# ArqSAME70Comp.net
KiCad netlist of a schematic drawn in EAGLE
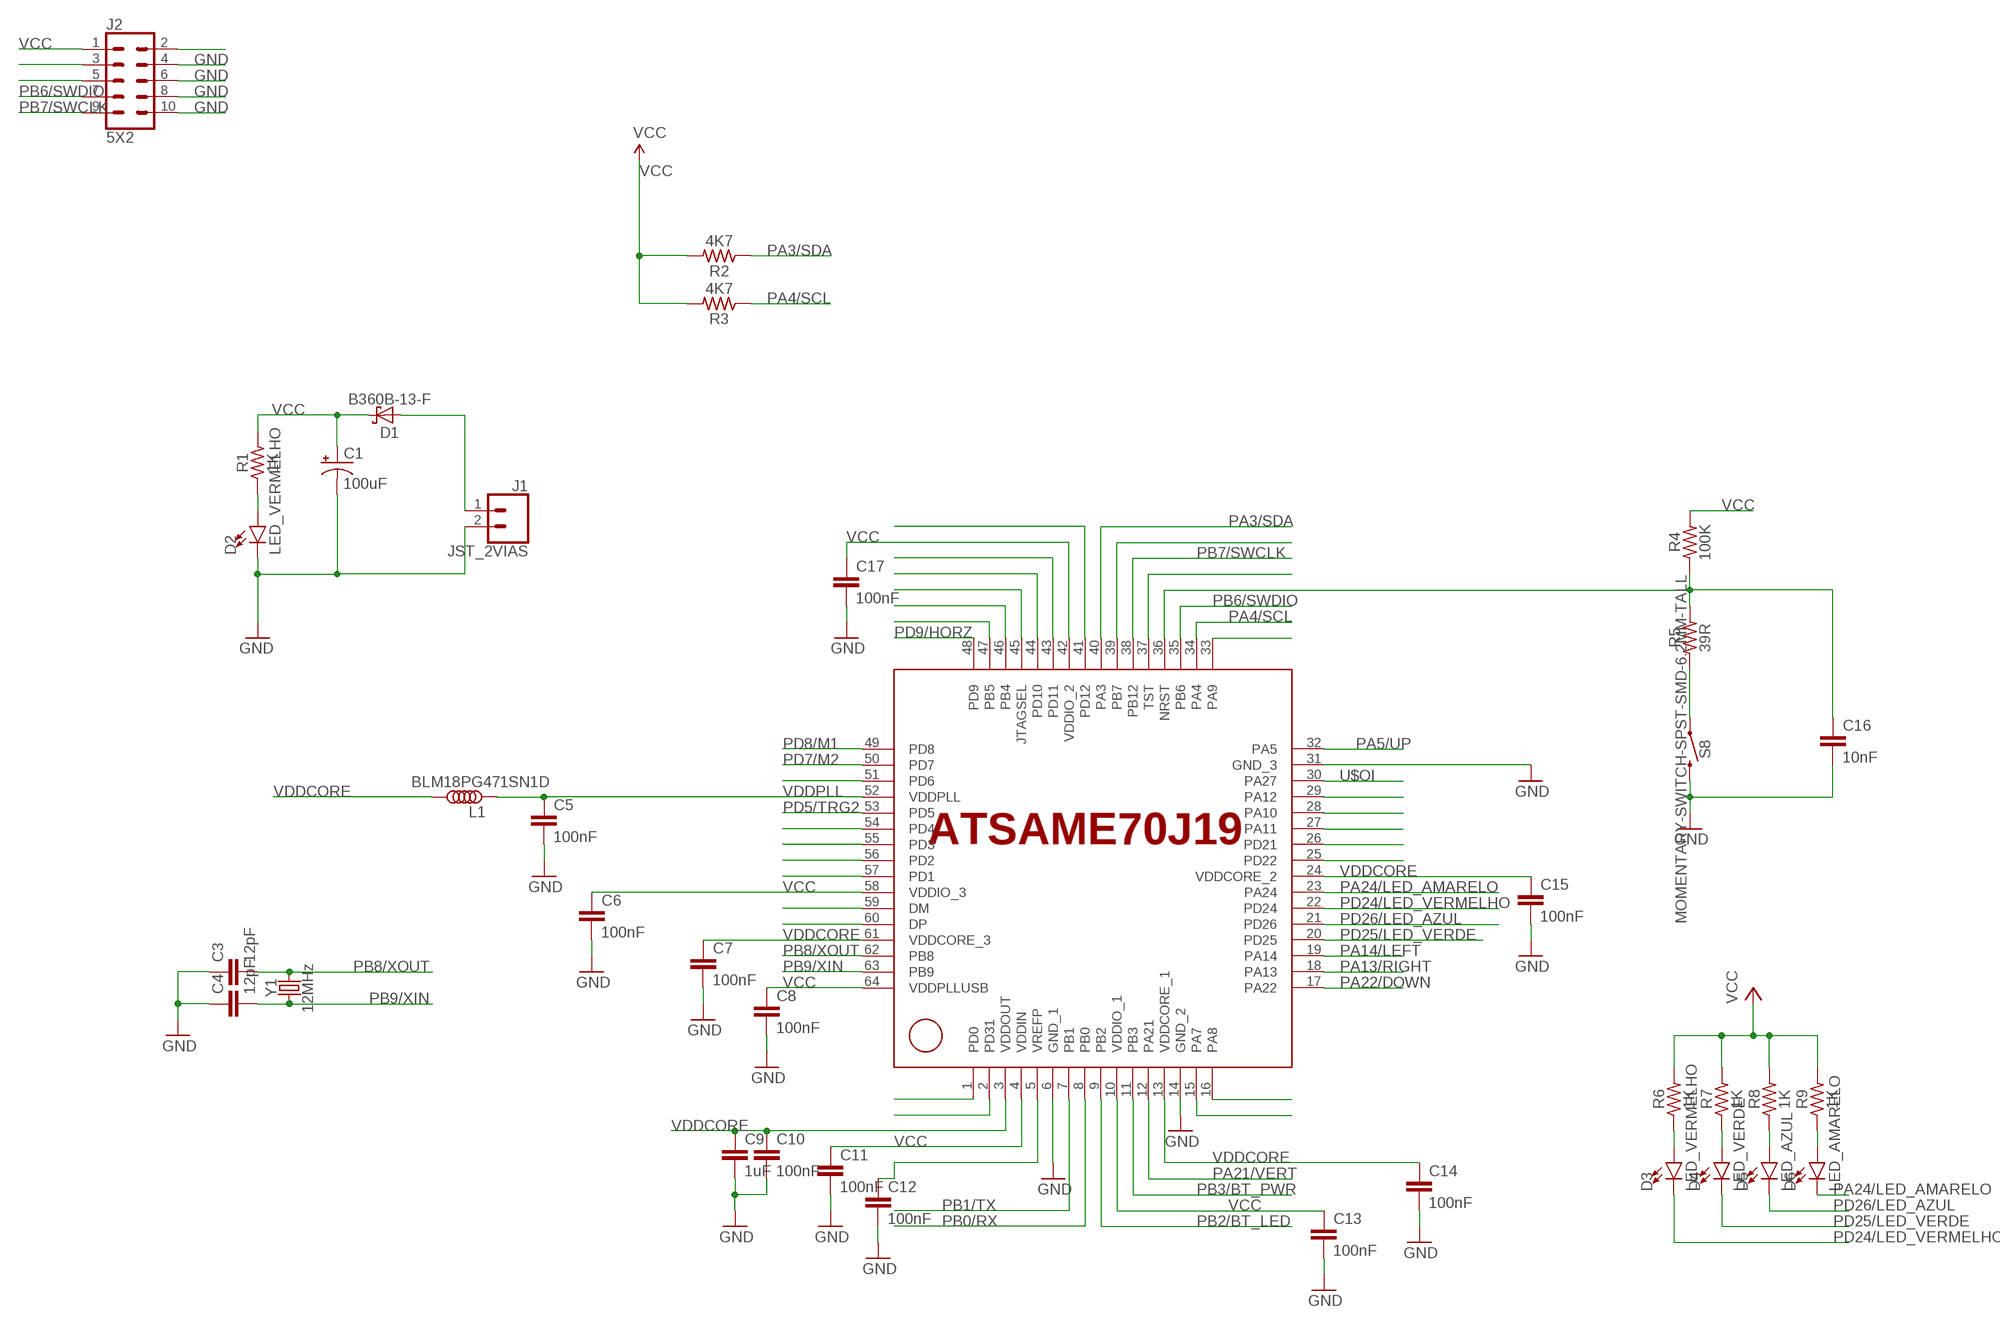
[diagram p0: schematic, sheet 1]

(export (version "E")
  (design (tool "Eeschema 10.0.6"))
  (components
    (comp (ref "C1")
      (value "100uF")
      (footprint "eagle-import:PANASONIC_D")
      (libsource (lib "eagle-import") (part "CAP_POLD"))
    )
    (comp (ref "C3")
      (value "12pF")
      (footprint "eagle-import:0603")
      (libsource (lib "eagle-import") (part "12PF-0603-50V-5%"))
    )
    (comp (ref "C4")
      (value "12pF")
      (footprint "eagle-import:0603")
      (libsource (lib "eagle-import") (part "12PF-0603-50V-5%"))
    )
    (comp (ref "C5")
      (value "100nF")
      (footprint "eagle-import:C0603K")
      (libsource (lib "eagle-import") (part "C-EUC0603K"))
    )
    (comp (ref "C6")
      (value "100nF")
      (footprint "eagle-import:C0603K")
      (libsource (lib "eagle-import") (part "C-EUC0603K"))
    )
    (comp (ref "C7")
      (value "100nF")
      (footprint "eagle-import:C0603K")
      (libsource (lib "eagle-import") (part "C-EUC0603K"))
    )
    (comp (ref "C8")
      (value "100nF")
      (footprint "eagle-import:C0603K")
      (libsource (lib "eagle-import") (part "C-EUC0603K"))
    )
    (comp (ref "C9")
      (value "1uF")
      (footprint "eagle-import:C0603K")
      (libsource (lib "eagle-import") (part "C-EUC0603K"))
    )
    (comp (ref "C10")
      (value "100nF")
      (footprint "eagle-import:C0603K")
      (libsource (lib "eagle-import") (part "C-EUC0603K"))
    )
    (comp (ref "C11")
      (value "100nF")
      (footprint "eagle-import:C0603K")
      (libsource (lib "eagle-import") (part "C-EUC0603K"))
    )
    (comp (ref "C12")
      (value "100nF")
      (footprint "eagle-import:C0603K")
      (libsource (lib "eagle-import") (part "C-EUC0603K"))
    )
    (comp (ref "C13")
      (value "100nF")
      (footprint "eagle-import:C0603K")
      (libsource (lib "eagle-import") (part "C-EUC0603K"))
    )
    (comp (ref "C14")
      (value "100nF")
      (footprint "eagle-import:C0603K")
      (libsource (lib "eagle-import") (part "C-EUC0603K"))
    )
    (comp (ref "C15")
      (value "100nF")
      (footprint "eagle-import:C0603K")
      (libsource (lib "eagle-import") (part "C-EUC0603K"))
    )
    (comp (ref "C16")
      (value "10nF")
      (footprint "eagle-import:C0603K")
      (libsource (lib "eagle-import") (part "C-EUC0603K"))
    )
    (comp (ref "C17")
      (value "100nF")
      (footprint "eagle-import:C0603K")
      (libsource (lib "eagle-import") (part "C-EUC0603K"))
    )
    (comp (ref "D1")
      (value "B360B-13-F")
      (footprint "eagle-import:DIODE_SMB")
      (libsource (lib "eagle-import") (part "SCHOTTKY-DIODE"))
    )
    (comp (ref "D2")
      (value "LED_VERMELHO")
      (footprint "eagle-import:LED-1206")
      (libsource (lib "eagle-import") (part "LED1206"))
    )
    (comp (ref "D3")
      (value "LED_VERMELHO")
      (footprint "eagle-import:LED-1206")
      (libsource (lib "eagle-import") (part "LED1206"))
    )
    (comp (ref "D4")
      (value "LED_VERDE")
      (footprint "eagle-import:LED-1206")
      (libsource (lib "eagle-import") (part "LED1206"))
    )
    (comp (ref "D5")
      (value "LED_AZUL")
      (footprint "eagle-import:LED-1206")
      (libsource (lib "eagle-import") (part "LED1206"))
    )
    (comp (ref "D6")
      (value "LED_AMARELO")
      (footprint "eagle-import:LED-1206")
      (libsource (lib "eagle-import") (part "LED1206"))
    )
    (comp (ref "J1")
      (value "JST_2VIAS")
      (footprint "eagle-import:JST-2-SMD")
      (libsource (lib "eagle-import") (part "CONN_02-JST-2MM-SMT"))
    )
    (comp (ref "J2")
      (value "5X2")
      (footprint "eagle-import:2X5")
      (libsource (lib "eagle-import") (part "CONN_5X2"))
    )
    (comp (ref "L1")
      (value "BLM18PG471SN1D")
      (footprint "eagle-import:PACKAGE_0603")
      (libsource (lib "eagle-import") (part "FERRITE_0603"))
    )
    (comp (ref "R1")
      (value "1K")
      (footprint "eagle-import:R0603")
      (libsource (lib "eagle-import") (part "R-US_R0603"))
    )
    (comp (ref "R2")
      (value "4K7")
      (footprint "eagle-import:R0603")
      (libsource (lib "eagle-import") (part "R-US_R0603"))
    )
    (comp (ref "R3")
      (value "4K7")
      (footprint "eagle-import:R0603")
      (libsource (lib "eagle-import") (part "R-US_R0603"))
    )
    (comp (ref "R4")
      (value "100K")
      (footprint "eagle-import:R0603")
      (libsource (lib "eagle-import") (part "R-US_R0603"))
    )
    (comp (ref "R5")
      (value "39R")
      (footprint "eagle-import:R0603")
      (libsource (lib "eagle-import") (part "R-US_R0603"))
    )
    (comp (ref "R6")
      (value "1K")
      (footprint "eagle-import:R0603")
      (libsource (lib "eagle-import") (part "R-US_R0603"))
    )
    (comp (ref "R7")
      (value "1K")
      (footprint "eagle-import:R0603")
      (libsource (lib "eagle-import") (part "R-US_R0603"))
    )
    (comp (ref "R8")
      (value "1K")
      (footprint "eagle-import:R0603")
      (libsource (lib "eagle-import") (part "R-US_R0603"))
    )
    (comp (ref "R9")
      (value "1K")
      (footprint "eagle-import:R0603")
      (libsource (lib "eagle-import") (part "R-US_R0603"))
    )
    (comp (ref "S8")
      (value "MOMENTARY-SWITCH-SPST-SMD-6.2MM-TALL")
      (footprint "eagle-import:TACTILE_SWITCH_SMD_6.2MM_TALL")
      (libsource (lib "eagle-import") (part "MOMENTARY-SWITCH-SPST-SMD-6.2MM-TALL"))
    )
    (comp (ref "UC")
      (value "ATSAME70J19_LQFP64")
      (footprint "eagle-import:LQFP64")
      (libsource (lib "eagle-import") (part "ATSAME70J19LQFP64"))
    )
    (comp (ref "Y1")
      (value "12MHz")
      (footprint "eagle-import:CRYSTAL-SMD-5X3.2-4PAD")
      (libsource (lib "eagle-import") (part "CRYSTAL-12MHZ{dblquote}"))
    )
  )
  (nets
    (net (code "1") (name "/PA3{slash}SDA") (class "Default")
      (node (ref "R2") (pin "1") (pinfunction "1_1") (pintype "passive"))
      (node (ref "UC") (pin "40") (pinfunction "PA3_40") (pintype "output"))
    )
    (net (code "2") (name "/PA4{slash}SCL") (class "Default")
      (node (ref "R3") (pin "1") (pinfunction "1_1") (pintype "passive"))
      (node (ref "UC") (pin "34") (pinfunction "PA4_34") (pintype "input"))
    )
    (net (code "3") (name "/PA5{slash}UP") (class "Default")
      (node (ref "UC") (pin "32") (pinfunction "PA5_32") (pintype "input"))
    )
    (net (code "4") (name "/PA13{slash}RIGHT") (class "Default")
      (node (ref "UC") (pin "18") (pinfunction "PA13_18") (pintype "power_in"))
    )
    (net (code "5") (name "/PA14{slash}LEFT") (class "Default")
      (node (ref "UC") (pin "19") (pinfunction "PA14_19") (pintype "output"))
    )
    (net (code "6") (name "/PA21{slash}VERT") (class "Default")
      (node (ref "UC") (pin "12") (pinfunction "PA21_12") (pintype "input"))
    )
    (net (code "7") (name "/PA22{slash}DOWN") (class "Default")
      (node (ref "UC") (pin "17") (pinfunction "PA22_17") (pintype "power_in"))
    )
    (net (code "8") (name "/PA24{slash}LED_AMARELO") (class "Default")
      (node (ref "D6") (pin "C") (pinfunction "C_C") (pintype "passive"))
      (node (ref "UC") (pin "23") (pinfunction "PA24_23") (pintype "output"))
    )
    (net (code "9") (name "/PB0{slash}RX") (class "Default")
      (node (ref "UC") (pin "8") (pinfunction "PB0_8") (pintype "output"))
    )
    (net (code "10") (name "/PB1{slash}TX") (class "Default")
      (node (ref "UC") (pin "7") (pinfunction "PB1_7") (pintype "output"))
    )
    (net (code "11") (name "/PB2{slash}BT_LED") (class "Default")
      (node (ref "UC") (pin "9") (pinfunction "PB2_9") (pintype "power_in"))
    )
    (net (code "12") (name "/PB3{slash}BT_PWR") (class "Default")
      (node (ref "UC") (pin "11") (pinfunction "PB3_11") (pintype "power_in"))
    )
    (net (code "13") (name "/PB6{slash}SWDIO") (class "Default")
      (node (ref "J2") (pin "7") (pinfunction "7_7") (pintype "passive"))
      (node (ref "UC") (pin "35") (pinfunction "PB6_35") (pintype "input"))
    )
    (net (code "14") (name "/PB7{slash}SWCLK") (class "Default")
      (node (ref "J2") (pin "9") (pinfunction "9_9") (pintype "passive"))
      (node (ref "UC") (pin "39") (pinfunction "PB7_39") (pintype "input"))
    )
    (net (code "15") (name "/PB8{slash}XOUT") (class "Default")
      (node (ref "C3") (pin "2") (pinfunction "2_2") (pintype "passive"))
      (node (ref "UC") (pin "62") (pinfunction "PB8_62") (pintype "output"))
      (node (ref "Y1") (pin "3") (pinfunction "2_3") (pintype "passive"))
    )
    (net (code "16") (name "/PB9{slash}XIN") (class "Default")
      (node (ref "C4") (pin "2") (pinfunction "2_2") (pintype "passive"))
      (node (ref "UC") (pin "63") (pinfunction "PB9_63") (pintype "output"))
      (node (ref "Y1") (pin "1") (pinfunction "1_1") (pintype "passive"))
    )
    (net (code "17") (name "/PD5{slash}TRG2") (class "Default")
      (node (ref "UC") (pin "53") (pinfunction "PD5_53") (pintype "input"))
    )
    (net (code "18") (name "/PD7{slash}M2") (class "Default")
      (node (ref "UC") (pin "50") (pinfunction "PD7_50") (pintype "input"))
    )
    (net (code "19") (name "/PD8{slash}M1") (class "Default")
      (node (ref "UC") (pin "49") (pinfunction "PD8_49") (pintype "input"))
    )
    (net (code "20") (name "/PD9{slash}HORZ") (class "Default")
      (node (ref "UC") (pin "48") (pinfunction "PD9_48") (pintype "input"))
    )
    (net (code "21") (name "/PD24{slash}LED_VERMELHO") (class "Default")
      (node (ref "D3") (pin "C") (pinfunction "C_C") (pintype "passive"))
      (node (ref "UC") (pin "22") (pinfunction "PD24_22") (pintype "power_in"))
    )
    (net (code "22") (name "/PD25{slash}LED_VERDE") (class "Default")
      (node (ref "D4") (pin "C") (pinfunction "C_C") (pintype "passive"))
      (node (ref "UC") (pin "20") (pinfunction "PD25_20") (pintype "input"))
    )
    (net (code "23") (name "/PD26{slash}LED_AZUL") (class "Default")
      (node (ref "D5") (pin "C") (pinfunction "C_C") (pintype "passive"))
      (node (ref "UC") (pin "21") (pinfunction "PD26_21") (pintype "power_in"))
    )
    (net (code "24") (name "/U$OI") (class "Default")
      (node (ref "UC") (pin "30") (pinfunction "PA27_30") (pintype "input"))
    )
    (net (code "25") (name "/VDDCORE") (class "Default")
      (node (ref "C10") (pin "1") (pinfunction "1_1") (pintype "passive"))
      (node (ref "C14") (pin "1") (pinfunction "1_1") (pintype "passive"))
      (node (ref "C15") (pin "1") (pinfunction "1_1") (pintype "passive"))
      (node (ref "C7") (pin "1") (pinfunction "1_1") (pintype "passive"))
      (node (ref "C9") (pin "1") (pinfunction "1_1") (pintype "passive"))
      (node (ref "L1") (pin "2") (pinfunction "2_2") (pintype "passive"))
      (node (ref "UC") (pin "13") (pinfunction "VDDCORE_1_13") (pintype "input"))
      (node (ref "UC") (pin "24") (pinfunction "VDDCORE_2_24") (pintype "output"))
      (node (ref "UC") (pin "3") (pinfunction "VDDOUT_3") (pintype "output"))
      (node (ref "UC") (pin "61") (pinfunction "VDDCORE_3_61") (pintype "output"))
    )
    (net (code "26") (name "/VDDPLL") (class "Default")
      (node (ref "C5") (pin "1") (pinfunction "1_1") (pintype "passive"))
      (node (ref "L1") (pin "1") (pinfunction "1_1") (pintype "passive"))
      (node (ref "UC") (pin "52") (pinfunction "VDDPLL_52") (pintype "input"))
    )
    (net (code "27") (name "GND") (class "Default")
      (node (ref "C1") (pin "-") (pinfunction "-_-") (pintype "passive"))
      (node (ref "C10") (pin "2") (pinfunction "2_2") (pintype "passive"))
      (node (ref "C11") (pin "2") (pinfunction "2_2") (pintype "passive"))
      (node (ref "C12") (pin "2") (pinfunction "2_2") (pintype "passive"))
      (node (ref "C13") (pin "2") (pinfunction "2_2") (pintype "passive"))
      (node (ref "C14") (pin "2") (pinfunction "2_2") (pintype "passive"))
      (node (ref "C15") (pin "2") (pinfunction "2_2") (pintype "passive"))
      (node (ref "C16") (pin "2") (pinfunction "2_2") (pintype "passive"))
      (node (ref "C17") (pin "2") (pinfunction "2_2") (pintype "passive"))
      (node (ref "C3") (pin "1") (pinfunction "1_1") (pintype "passive"))
      (node (ref "C4") (pin "1") (pinfunction "1_1") (pintype "passive"))
      (node (ref "C5") (pin "2") (pinfunction "2_2") (pintype "passive"))
      (node (ref "C6") (pin "2") (pinfunction "2_2") (pintype "passive"))
      (node (ref "C7") (pin "2") (pinfunction "2_2") (pintype "passive"))
      (node (ref "C8") (pin "2") (pinfunction "2_2") (pintype "passive"))
      (node (ref "C9") (pin "2") (pinfunction "2_2") (pintype "passive"))
      (node (ref "D2") (pin "C") (pinfunction "C_C") (pintype "passive"))
      (node (ref "J1") (pin "2") (pinfunction "1_2") (pintype "passive"))
      (node (ref "J2") (pin "10") (pinfunction "10_10") (pintype "passive"))
      (node (ref "J2") (pin "4") (pinfunction "4_4") (pintype "passive"))
      (node (ref "J2") (pin "6") (pinfunction "6_6") (pintype "passive"))
      (node (ref "J2") (pin "8") (pinfunction "8_8") (pintype "passive"))
      (node (ref "S8") (pin "B2") (pinfunction "2_B2") (pintype "passive"))
      (node (ref "UC") (pin "14") (pinfunction "GND_2_14") (pintype "input"))
      (node (ref "UC") (pin "31") (pinfunction "GND_3_31") (pintype "input"))
      (node (ref "UC") (pin "6") (pinfunction "GND_1_6") (pintype "output"))
    )
    (net (code "28") (name "Net-(D1-C)") (class "Default")
      (node (ref "D1") (pin "A") (pinfunction "C_A") (pintype "passive"))
      (node (ref "J1") (pin "1") (pinfunction "2_1") (pintype "passive"))
    )
    (net (code "29") (name "Net-(D2-PadA)") (class "Default")
      (node (ref "D2") (pin "A") (pinfunction "A_A") (pintype "passive"))
      (node (ref "R1") (pin "1") (pinfunction "1_1") (pintype "passive"))
    )
    (net (code "30") (name "Net-(D3-PadA)") (class "Default")
      (node (ref "D3") (pin "A") (pinfunction "A_A") (pintype "passive"))
      (node (ref "R6") (pin "1") (pinfunction "1_1") (pintype "passive"))
    )
    (net (code "31") (name "Net-(D4-PadA)") (class "Default")
      (node (ref "D4") (pin "A") (pinfunction "A_A") (pintype "passive"))
      (node (ref "R7") (pin "1") (pinfunction "1_1") (pintype "passive"))
    )
    (net (code "32") (name "Net-(D5-PadA)") (class "Default")
      (node (ref "D5") (pin "A") (pinfunction "A_A") (pintype "passive"))
      (node (ref "R8") (pin "1") (pinfunction "1_1") (pintype "passive"))
    )
    (net (code "33") (name "Net-(D6-PadA)") (class "Default")
      (node (ref "D6") (pin "A") (pinfunction "A_A") (pintype "passive"))
      (node (ref "R9") (pin "1") (pinfunction "1_1") (pintype "passive"))
    )
    (net (code "34") (name "Net-(S8-1)") (class "Default")
      (node (ref "R5") (pin "1") (pinfunction "1_1") (pintype "passive"))
      (node (ref "S8") (pin "A2") (pinfunction "1_A2") (pintype "passive"))
    )
    (net (code "35") (name "Net-(UC-NRST)") (class "Default")
      (node (ref "C16") (pin "1") (pinfunction "1_1") (pintype "passive"))
      (node (ref "R4") (pin "1") (pinfunction "1_1") (pintype "passive"))
      (node (ref "R5") (pin "2") (pinfunction "2_2") (pintype "passive"))
      (node (ref "UC") (pin "36") (pinfunction "NRST_36") (pintype "power_in"))
    )
    (net (code "36") (name "Net-(UC-VREFP)") (class "Default")
      (node (ref "C12") (pin "1") (pinfunction "1_1") (pintype "passive"))
      (node (ref "UC") (pin "5") (pinfunction "VREFP_5") (pintype "output"))
    )
    (net (code "37") (name "VCC") (class "Default")
      (node (ref "C1") (pin "+") (pinfunction "+_+") (pintype "passive"))
      (node (ref "C11") (pin "1") (pinfunction "1_1") (pintype "passive"))
      (node (ref "C13") (pin "1") (pinfunction "1_1") (pintype "passive"))
      (node (ref "C17") (pin "1") (pinfunction "1_1") (pintype "passive"))
      (node (ref "C6") (pin "1") (pinfunction "1_1") (pintype "passive"))
      (node (ref "C8") (pin "1") (pinfunction "1_1") (pintype "passive"))
      (node (ref "D1") (pin "C") (pinfunction "A_C") (pintype "passive"))
      (node (ref "J2") (pin "1") (pinfunction "1_1") (pintype "passive"))
      (node (ref "R1") (pin "2") (pinfunction "2_2") (pintype "passive"))
      (node (ref "R2") (pin "2") (pinfunction "2_2") (pintype "passive"))
      (node (ref "R3") (pin "2") (pinfunction "2_2") (pintype "passive"))
      (node (ref "R4") (pin "2") (pinfunction "2_2") (pintype "passive"))
      (node (ref "R6") (pin "2") (pinfunction "2_2") (pintype "passive"))
      (node (ref "R7") (pin "2") (pinfunction "2_2") (pintype "passive"))
      (node (ref "R8") (pin "2") (pinfunction "2_2") (pintype "passive"))
      (node (ref "R9") (pin "2") (pinfunction "2_2") (pintype "passive"))
      (node (ref "UC") (pin "10") (pinfunction "VDDIO_1_10") (pintype "input"))
      (node (ref "UC") (pin "4") (pinfunction "VDDIN_4") (pintype "output"))
      (node (ref "UC") (pin "42") (pinfunction "VDDIO_2_42") (pintype "output"))
      (node (ref "UC") (pin "58") (pinfunction "VDDIO_3_58") (pintype "input"))
      (node (ref "UC") (pin "64") (pinfunction "VDDPLLUSB_64") (pintype "input"))
    )
    (net (code "38") (name "unconnected-(J2-Pad2)") (class "Default")
      (node (ref "J2") (pin "2") (pinfunction "2_2") (pintype "passive"))
    )
    (net (code "39") (name "unconnected-(J2-Pad3)") (class "Default")
      (node (ref "J2") (pin "3") (pinfunction "3_3") (pintype "passive"))
    )
    (net (code "40") (name "unconnected-(J2-Pad5)") (class "Default")
      (node (ref "J2") (pin "5") (pinfunction "5_5") (pintype "passive"))
    )
    (net (code "41") (name "unconnected-(UC-DM-Pad59)") (class "Default")
      (node (ref "UC") (pin "59") (pinfunction "DM_59") (pintype "input"))
    )
    (net (code "42") (name "unconnected-(UC-DP-Pad60)") (class "Default")
      (node (ref "UC") (pin "60") (pinfunction "DP_60") (pintype "input"))
    )
    (net (code "43") (name "unconnected-(UC-JTAGSEL-Pad45)") (class "Default")
      (node (ref "UC") (pin "45") (pinfunction "JTAGSEL_45") (pintype "power_in"))
    )
    (net (code "44") (name "unconnected-(UC-PA7-Pad15)") (class "Default")
      (node (ref "UC") (pin "15") (pinfunction "PA7_15") (pintype "output"))
    )
    (net (code "45") (name "unconnected-(UC-PA8-Pad16)") (class "Default")
      (node (ref "UC") (pin "16") (pinfunction "PA8_16") (pintype "output"))
    )
    (net (code "46") (name "unconnected-(UC-PA9-Pad33)") (class "Default")
      (node (ref "UC") (pin "33") (pinfunction "PA9_33") (pintype "power_in"))
    )
    (net (code "47") (name "unconnected-(UC-PA10-Pad28)") (class "Default")
      (node (ref "UC") (pin "28") (pinfunction "PA10_28") (pintype "output"))
    )
    (net (code "48") (name "unconnected-(UC-PA11-Pad27)") (class "Default")
      (node (ref "UC") (pin "27") (pinfunction "PA11_27") (pintype "input"))
    )
    (net (code "49") (name "unconnected-(UC-PA12-Pad29)") (class "Default")
      (node (ref "UC") (pin "29") (pinfunction "PA12_29") (pintype "output"))
    )
    (net (code "50") (name "unconnected-(UC-PB4-Pad46)") (class "Default")
      (node (ref "UC") (pin "46") (pinfunction "PB4_46") (pintype "power_in"))
    )
    (net (code "51") (name "unconnected-(UC-PB5-Pad47)") (class "Default")
      (node (ref "UC") (pin "47") (pinfunction "PB5_47") (pintype "input"))
    )
    (net (code "52") (name "unconnected-(UC-PB12-Pad38)") (class "Default")
      (node (ref "UC") (pin "38") (pinfunction "PB12_38") (pintype "input"))
    )
    (net (code "53") (name "unconnected-(UC-PD0-Pad1)") (class "Default")
      (node (ref "UC") (pin "1") (pinfunction "PD0_1") (pintype "input"))
    )
    (net (code "54") (name "unconnected-(UC-PD1-Pad57)") (class "Default")
      (node (ref "UC") (pin "57") (pinfunction "PD1_57") (pintype "input"))
    )
    (net (code "55") (name "unconnected-(UC-PD2-Pad56)") (class "Default")
      (node (ref "UC") (pin "56") (pinfunction "PD2_56") (pintype "power_in"))
    )
    (net (code "56") (name "unconnected-(UC-PD3-Pad55)") (class "Default")
      (node (ref "UC") (pin "55") (pinfunction "PD3_55") (pintype "power_in"))
    )
    (net (code "57") (name "unconnected-(UC-PD4-Pad54)") (class "Default")
      (node (ref "UC") (pin "54") (pinfunction "PD4_54") (pintype "power_in"))
    )
    (net (code "58") (name "unconnected-(UC-PD6-Pad51)") (class "Default")
      (node (ref "UC") (pin "51") (pinfunction "PD6_51") (pintype "input"))
    )
    (net (code "59") (name "unconnected-(UC-PD10-Pad44)") (class "Default")
      (node (ref "UC") (pin "44") (pinfunction "PD10_44") (pintype "output"))
    )
    (net (code "60") (name "unconnected-(UC-PD11-Pad43)") (class "Default")
      (node (ref "UC") (pin "43") (pinfunction "PD11_43") (pintype "input"))
    )
    (net (code "61") (name "unconnected-(UC-PD12-Pad41)") (class "Default")
      (node (ref "UC") (pin "41") (pinfunction "PD12_41") (pintype "input"))
    )
    (net (code "62") (name "unconnected-(UC-PD21-Pad26)") (class "Default")
      (node (ref "UC") (pin "26") (pinfunction "PD21_26") (pintype "input"))
    )
    (net (code "63") (name "unconnected-(UC-PD22-Pad25)") (class "Default")
      (node (ref "UC") (pin "25") (pinfunction "PD22_25") (pintype "input"))
    )
    (net (code "64") (name "unconnected-(UC-PD31-Pad2)") (class "Default")
      (node (ref "UC") (pin "2") (pinfunction "PD31_2") (pintype "output"))
    )
    (net (code "65") (name "unconnected-(UC-TST-Pad37)") (class "Default")
      (node (ref "UC") (pin "37") (pinfunction "TST_37") (pintype "output"))
    )
  )
)
